# EDR_2-schematic.net
KiCad netlist of a schematic drawn in Altium Designer
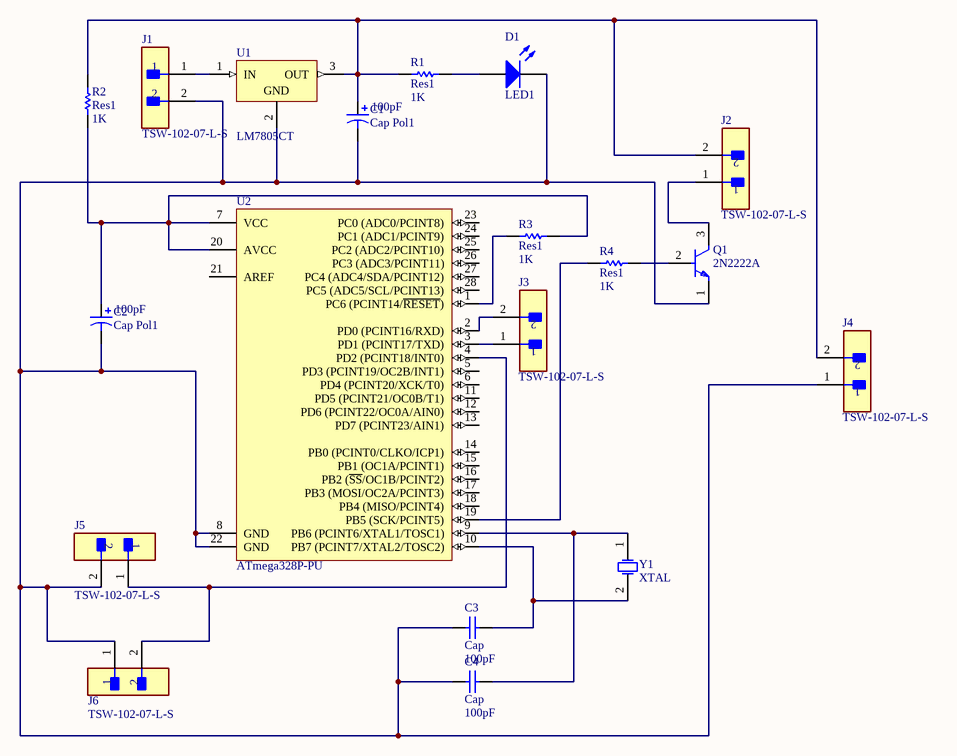
[diagram p0: EDR_2-schematic.SchDoc]

(export (version "E")
  (design (tool "Eeschema 10.0.6"))
  (components
    (comp (ref "C1")
      (value "Cap Pol1")
      (footprint "RB7.6-15")
      (description "Polarized Capacitor (Radial)")
      (fields (field (name "ALTIUM_VALUE") "100pF") (field (name "PUBLISHER") "Altium Limited"))
      (libsource (lib "Miscellaneous Devices") (part "Cap Pol1"))
    )
    (comp (ref "C2")
      (value "Cap Pol1")
      (footprint "RB7.6-15")
      (description "Polarized Capacitor (Radial)")
      (fields (field (name "ALTIUM_VALUE") "100pF") (field (name "PUBLISHER") "Altium Limited"))
      (libsource (lib "Miscellaneous Devices") (part "Cap Pol1"))
    )
    (comp (ref "C3")
      (value "Cap")
      (footprint "RAD-0.3")
      (description "Capacitor")
      (fields (field (name "ALTIUM_VALUE") "100pF") (field (name "PUBLISHER") "Altium Limited"))
      (libsource (lib "Miscellaneous Devices") (part "Cap"))
    )
    (comp (ref "C4")
      (value "Cap")
      (footprint "RAD-0.3")
      (description "Capacitor")
      (fields (field (name "ALTIUM_VALUE") "100pF") (field (name "PUBLISHER") "Altium Limited"))
      (libsource (lib "Miscellaneous Devices") (part "Cap"))
    )
    (comp (ref "D1")
      (value "LED1")
      (footprint "LED-1")
      (description "Typical RED GaAs LED")
      (fields (field (name "PUBLISHER") "Altium Limited"))
      (libsource (lib "Miscellaneous Devices") (part "LED1"))
    )
    (comp (ref "J1")
      (value "TSW-102-07-L-S")
      (footprint "FP-TSW-102-07-L-S-MFG")
      (description "CONN HEADER VERT 2POS 2.54MM")
      (libsource (lib "Altium Content Vault") (part "3bc925449376181038e59eaffc5286c"))
    )
    (comp (ref "J2")
      (value "TSW-102-07-L-S")
      (footprint "FP-TSW-102-07-L-S-MFG")
      (description "CONN HEADER VERT 2POS 2.54MM")
      (libsource (lib "") (part "3bc925449376181038e59eaffc5286c_1"))
    )
    (comp (ref "J3")
      (value "TSW-102-07-L-S")
      (footprint "FP-TSW-102-07-L-S-MFG")
      (description "CONN HEADER VERT 2POS 2.54MM")
      (libsource (lib "") (part "3bc925449376181038e59eaffc5286c_1"))
    )
    (comp (ref "J4")
      (value "TSW-102-07-L-S")
      (footprint "FP-TSW-102-07-L-S-MFG")
      (description "CONN HEADER VERT 2POS 2.54MM")
      (libsource (lib "") (part "3bc925449376181038e59eaffc5286c_1"))
    )
    (comp (ref "J5")
      (value "TSW-102-07-L-S")
      (footprint "FP-TSW-102-07-L-S-MFG")
      (description "CONN HEADER VERT 2POS 2.54MM")
      (libsource (lib "") (part "3bc925449376181038e59eaffc5286c_2"))
    )
    (comp (ref "J6")
      (value "TSW-102-07-L-S")
      (footprint "FP-TSW-102-07-L-S-MFG")
      (description "CONN HEADER VERT 2POS 2.54MM")
      (libsource (lib "") (part "3bc925449376181038e59eaffc5286c_3"))
    )
    (comp (ref "Q1")
      (value "2N2222A")
      (footprint "FP-2N2222A-MFG")
      (description "T-NPN SI- AUDIO VHF AMP")
      (libsource (lib "Altium Content Vault") (part "a64cbfbad643015290886283bc510aa"))
    )
    (comp (ref "R1")
      (value "Res1")
      (footprint "AXIAL-0.3")
      (description "Resistor")
      (fields (field (name "ALTIUM_VALUE") "1K") (field (name "PUBLISHER") "Altium Limited"))
      (libsource (lib "Miscellaneous Devices") (part "Res1"))
    )
    (comp (ref "R2")
      (value "Res1")
      (footprint "AXIAL-0.3")
      (description "Resistor")
      (fields (field (name "ALTIUM_VALUE") "1K") (field (name "PUBLISHER") "Altium Limited"))
      (libsource (lib "Miscellaneous Devices") (part "Res1"))
    )
    (comp (ref "R3")
      (value "Res1")
      (footprint "AXIAL-0.3")
      (description "Resistor")
      (fields (field (name "ALTIUM_VALUE") "1K") (field (name "PUBLISHER") "Altium Limited"))
      (libsource (lib "Miscellaneous Devices") (part "Res1"))
    )
    (comp (ref "R4")
      (value "Res1")
      (footprint "AXIAL-0.3")
      (description "Resistor")
      (fields (field (name "ALTIUM_VALUE") "1K") (field (name "PUBLISHER") "Altium Limited"))
      (libsource (lib "Miscellaneous Devices") (part "Res1"))
    )
    (comp (ref "U1")
      (value "LM7805CT")
      (footprint "FAIR-TO-220-3")
      (description "Positive Voltage Regulator, 5 V, 1 A, -40 to 125 degC, 3-Pin TO-220, RoHS, Tube")
      (fields (field (name "MANUFACTURER") "FairchildSemiconductor"))
      (libsource (lib "Altium Content Vault") (part "FAIR-LM7805CT-TO220-3"))
    )
    (comp (ref "U2")
      (value "ATmega328P-PU")
      (footprint "28P3")
      (libsource (lib "Altium Content Vault") (part "MC-8B-ATM48-IL28"))
    )
    (comp (ref "Y1")
      (value "XTAL")
      (footprint "R38")
      (description "Crystal Oscillator")
      (fields (field (name "PUBLISHER") "Altium Limited"))
      (libsource (lib "Miscellaneous Devices") (part "XTAL"))
    )
  )
  (nets
    (net (code "1") (name "Net-(D1-A)") (class "Default")
      (node (ref "D1") (pin "1") (pinfunction "A_1") (pintype "passive"))
      (node (ref "R1") (pin "2") (pinfunction "2_2") (pintype "passive"))
    )
    (net (code "2") (name "Net-(D1-K)") (class "Default")
      (node (ref "C1") (pin "2") (pinfunction "2_2") (pintype "passive"))
      (node (ref "C2") (pin "2") (pinfunction "2_2") (pintype "passive"))
      (node (ref "C3") (pin "1") (pinfunction "1_1") (pintype "passive"))
      (node (ref "C4") (pin "1") (pinfunction "1_1") (pintype "passive"))
      (node (ref "D1") (pin "2") (pinfunction "K_2") (pintype "passive"))
      (node (ref "J1") (pin "2") (pinfunction "2_2") (pintype "passive"))
      (node (ref "J4") (pin "1") (pinfunction "1_1") (pintype "passive"))
      (node (ref "J5") (pin "2") (pinfunction "2_2") (pintype "passive"))
      (node (ref "J6") (pin "1") (pinfunction "1_1") (pintype "passive"))
      (node (ref "Q1") (pin "1") (pinfunction "E_1") (pintype "passive"))
      (node (ref "U1") (pin "2") (pinfunction "GND_2") (pintype "power_in"))
      (node (ref "U2") (pin "22") (pinfunction "GND_22") (pintype "power_in"))
      (node (ref "U2") (pin "8") (pinfunction "GND_8") (pintype "power_in"))
    )
    (net (code "3") (name "Net-(Q1-B)") (class "Default")
      (node (ref "Q1") (pin "2") (pinfunction "B_2") (pintype "passive"))
      (node (ref "R4") (pin "2") (pinfunction "2_2") (pintype "passive"))
    )
    (net (code "4") (name "Net-(Q1-C)") (class "Default")
      (node (ref "J2") (pin "1") (pinfunction "1_1") (pintype "passive"))
      (node (ref "Q1") (pin "3") (pinfunction "C_3") (pintype "passive"))
    )
    (net (code "5") (name "Net-(U1-IN)") (class "Default")
      (node (ref "J1") (pin "1") (pinfunction "1_1") (pintype "passive"))
      (node (ref "U1") (pin "1") (pinfunction "IN_1") (pintype "input"))
    )
    (net (code "6") (name "Net-(U1-OUT)") (class "Default")
      (node (ref "C1") (pin "1") (pinfunction "1_1") (pintype "passive"))
      (node (ref "J2") (pin "2") (pinfunction "2_2") (pintype "passive"))
      (node (ref "J4") (pin "2") (pinfunction "2_2") (pintype "passive"))
      (node (ref "R1") (pin "1") (pinfunction "1_1") (pintype "passive"))
      (node (ref "R2") (pin "1") (pinfunction "1_1") (pintype "passive"))
      (node (ref "U1") (pin "3") (pinfunction "OUT_3") (pintype "output"))
    )
    (net (code "7") (name "Net-(U2-AVCC)") (class "Default")
      (node (ref "C2") (pin "1") (pinfunction "1_1") (pintype "passive"))
      (node (ref "R2") (pin "2") (pinfunction "2_2") (pintype "passive"))
      (node (ref "R3") (pin "2") (pinfunction "2_2") (pintype "passive"))
      (node (ref "U2") (pin "20") (pinfunction "AVCC_20") (pintype "power_in"))
      (node (ref "U2") (pin "7") (pinfunction "VCC_7") (pintype "power_in"))
    )
    (net (code "8") (name "Net-(U2-PB5_(SCK{slash}PCINT5))") (class "Default")
      (node (ref "R4") (pin "1") (pinfunction "1_1") (pintype "passive"))
      (node (ref "U2") (pin "19") (pinfunction "PB5_(SCK/PCINT5)_19") (pintype "bidirectional"))
    )
    (net (code "9") (name "Net-(U2-PB6_(PCINT6{slash}XTAL1{slash}TOSC1))") (class "Default")
      (node (ref "C4") (pin "2") (pinfunction "2_2") (pintype "passive"))
      (node (ref "U2") (pin "9") (pinfunction "PB6_(PCINT6/XTAL1/TOSC1)_9") (pintype "bidirectional"))
      (node (ref "Y1") (pin "1") (pinfunction "OSC1_1") (pintype "passive"))
    )
    (net (code "10") (name "Net-(U2-PB7_(PCINT7{slash}XTAL2{slash}TOSC2))") (class "Default")
      (node (ref "C3") (pin "2") (pinfunction "2_2") (pintype "passive"))
      (node (ref "U2") (pin "10") (pinfunction "PB7_(PCINT7/XTAL2/TOSC2)_10") (pintype "bidirectional"))
      (node (ref "Y1") (pin "2") (pinfunction "OSC2_2") (pintype "passive"))
    )
    (net (code "11") (name "Net-(U2-PC6_(PCINT14{slash}~{RESET}))") (class "Default")
      (node (ref "R3") (pin "1") (pinfunction "1_1") (pintype "passive"))
      (node (ref "U2") (pin "1") (pinfunction "PC6_(PCINT14/~{RESET})_1") (pintype "bidirectional"))
    )
    (net (code "12") (name "Net-(U2-PD0_(PCINT16{slash}RXD))") (class "Default")
      (node (ref "J3") (pin "2") (pinfunction "2_2") (pintype "passive"))
      (node (ref "U2") (pin "2") (pinfunction "PD0_(PCINT16/RXD)_2") (pintype "bidirectional"))
    )
    (net (code "13") (name "Net-(U2-PD1_(PCINT17{slash}TXD))") (class "Default")
      (node (ref "J3") (pin "1") (pinfunction "1_1") (pintype "passive"))
      (node (ref "U2") (pin "3") (pinfunction "PD1_(PCINT17/TXD)_3") (pintype "bidirectional"))
    )
    (net (code "14") (name "Net-(U2-PD2_(PCINT18{slash}INT0))") (class "Default")
      (node (ref "J5") (pin "1") (pinfunction "1_1") (pintype "passive"))
      (node (ref "J6") (pin "2") (pinfunction "2_2") (pintype "passive"))
      (node (ref "U2") (pin "4") (pinfunction "PD2_(PCINT18/INT0)_4") (pintype "bidirectional"))
    )
    (net (code "15") (name "unconnected-(U2-AREF-Pad21)") (class "Default")
      (node (ref "U2") (pin "21") (pinfunction "AREF_21") (pintype "power_in"))
    )
    (net (code "16") (name "unconnected-(U2-PB0_(PCINT0{slash}CLKO{slash}ICP1)-Pad14)") (class "Default")
      (node (ref "U2") (pin "14") (pinfunction "PB0_(PCINT0/CLKO/ICP1)_14") (pintype "bidirectional"))
    )
    (net (code "17") (name "unconnected-(U2-PB1_(OC1A{slash}PCINT1)-Pad15)") (class "Default")
      (node (ref "U2") (pin "15") (pinfunction "PB1_(OC1A/PCINT1)_15") (pintype "bidirectional"))
    )
    (net (code "18") (name "unconnected-(U2-PB2_(~{SS}{slash}OC1B{slash}PCINT2)-Pad16)") (class "Default")
      (node (ref "U2") (pin "16") (pinfunction "PB2_(~{SS}/OC1B/PCINT2)_16") (pintype "bidirectional"))
    )
    (net (code "19") (name "unconnected-(U2-PB3_(MOSI{slash}OC2A{slash}PCINT3)-Pad17)") (class "Default")
      (node (ref "U2") (pin "17") (pinfunction "PB3_(MOSI/OC2A/PCINT3)_17") (pintype "bidirectional"))
    )
    (net (code "20") (name "unconnected-(U2-PB4_(MISO{slash}PCINT4)-Pad18)") (class "Default")
      (node (ref "U2") (pin "18") (pinfunction "PB4_(MISO/PCINT4)_18") (pintype "bidirectional"))
    )
    (net (code "21") (name "unconnected-(U2-PC0_(ADC0{slash}PCINT8)-Pad23)") (class "Default")
      (node (ref "U2") (pin "23") (pinfunction "PC0_(ADC0/PCINT8)_23") (pintype "bidirectional"))
    )
    (net (code "22") (name "unconnected-(U2-PC1_(ADC1{slash}PCINT9)-Pad24)") (class "Default")
      (node (ref "U2") (pin "24") (pinfunction "PC1_(ADC1/PCINT9)_24") (pintype "bidirectional"))
    )
    (net (code "23") (name "unconnected-(U2-PC2_(ADC2{slash}PCINT10)-Pad25)") (class "Default")
      (node (ref "U2") (pin "25") (pinfunction "PC2_(ADC2/PCINT10)_25") (pintype "bidirectional"))
    )
    (net (code "24") (name "unconnected-(U2-PC3_(ADC3{slash}PCINT11)-Pad26)") (class "Default")
      (node (ref "U2") (pin "26") (pinfunction "PC3_(ADC3/PCINT11)_26") (pintype "bidirectional"))
    )
    (net (code "25") (name "unconnected-(U2-PC4_(ADC4{slash}SDA{slash}PCINT12)-Pad27)") (class "Default")
      (node (ref "U2") (pin "27") (pinfunction "PC4_(ADC4/SDA/PCINT12)_27") (pintype "bidirectional"))
    )
    (net (code "26") (name "unconnected-(U2-PC5_(ADC5{slash}SCL{slash}PCINT13)-Pad28)") (class "Default")
      (node (ref "U2") (pin "28") (pinfunction "PC5_(ADC5/SCL/PCINT13)_28") (pintype "bidirectional"))
    )
    (net (code "27") (name "unconnected-(U2-PD3_(PCINT19{slash}OC2B{slash}INT1)-Pad5)") (class "Default")
      (node (ref "U2") (pin "5") (pinfunction "PD3_(PCINT19/OC2B/INT1)_5") (pintype "bidirectional"))
    )
    (net (code "28") (name "unconnected-(U2-PD4_(PCINT20{slash}XCK{slash}T0)-Pad6)") (class "Default")
      (node (ref "U2") (pin "6") (pinfunction "PD4_(PCINT20/XCK/T0)_6") (pintype "bidirectional"))
    )
    (net (code "29") (name "unconnected-(U2-PD5_(PCINT21{slash}OC0B{slash}T1)-Pad11)") (class "Default")
      (node (ref "U2") (pin "11") (pinfunction "PD5_(PCINT21/OC0B/T1)_11") (pintype "bidirectional"))
    )
    (net (code "30") (name "unconnected-(U2-PD6_(PCINT22{slash}OC0A{slash}AIN0)-Pad12)") (class "Default")
      (node (ref "U2") (pin "12") (pinfunction "PD6_(PCINT22/OC0A/AIN0)_12") (pintype "bidirectional"))
    )
    (net (code "31") (name "unconnected-(U2-PD7_(PCINT23{slash}AIN1)-Pad13)") (class "Default")
      (node (ref "U2") (pin "13") (pinfunction "PD7_(PCINT23/AIN1)_13") (pintype "bidirectional"))
    )
  )
)
